# SBC_TMS9918A_ISA.net
KiCad netlist of a schematic drawn in EAGLE
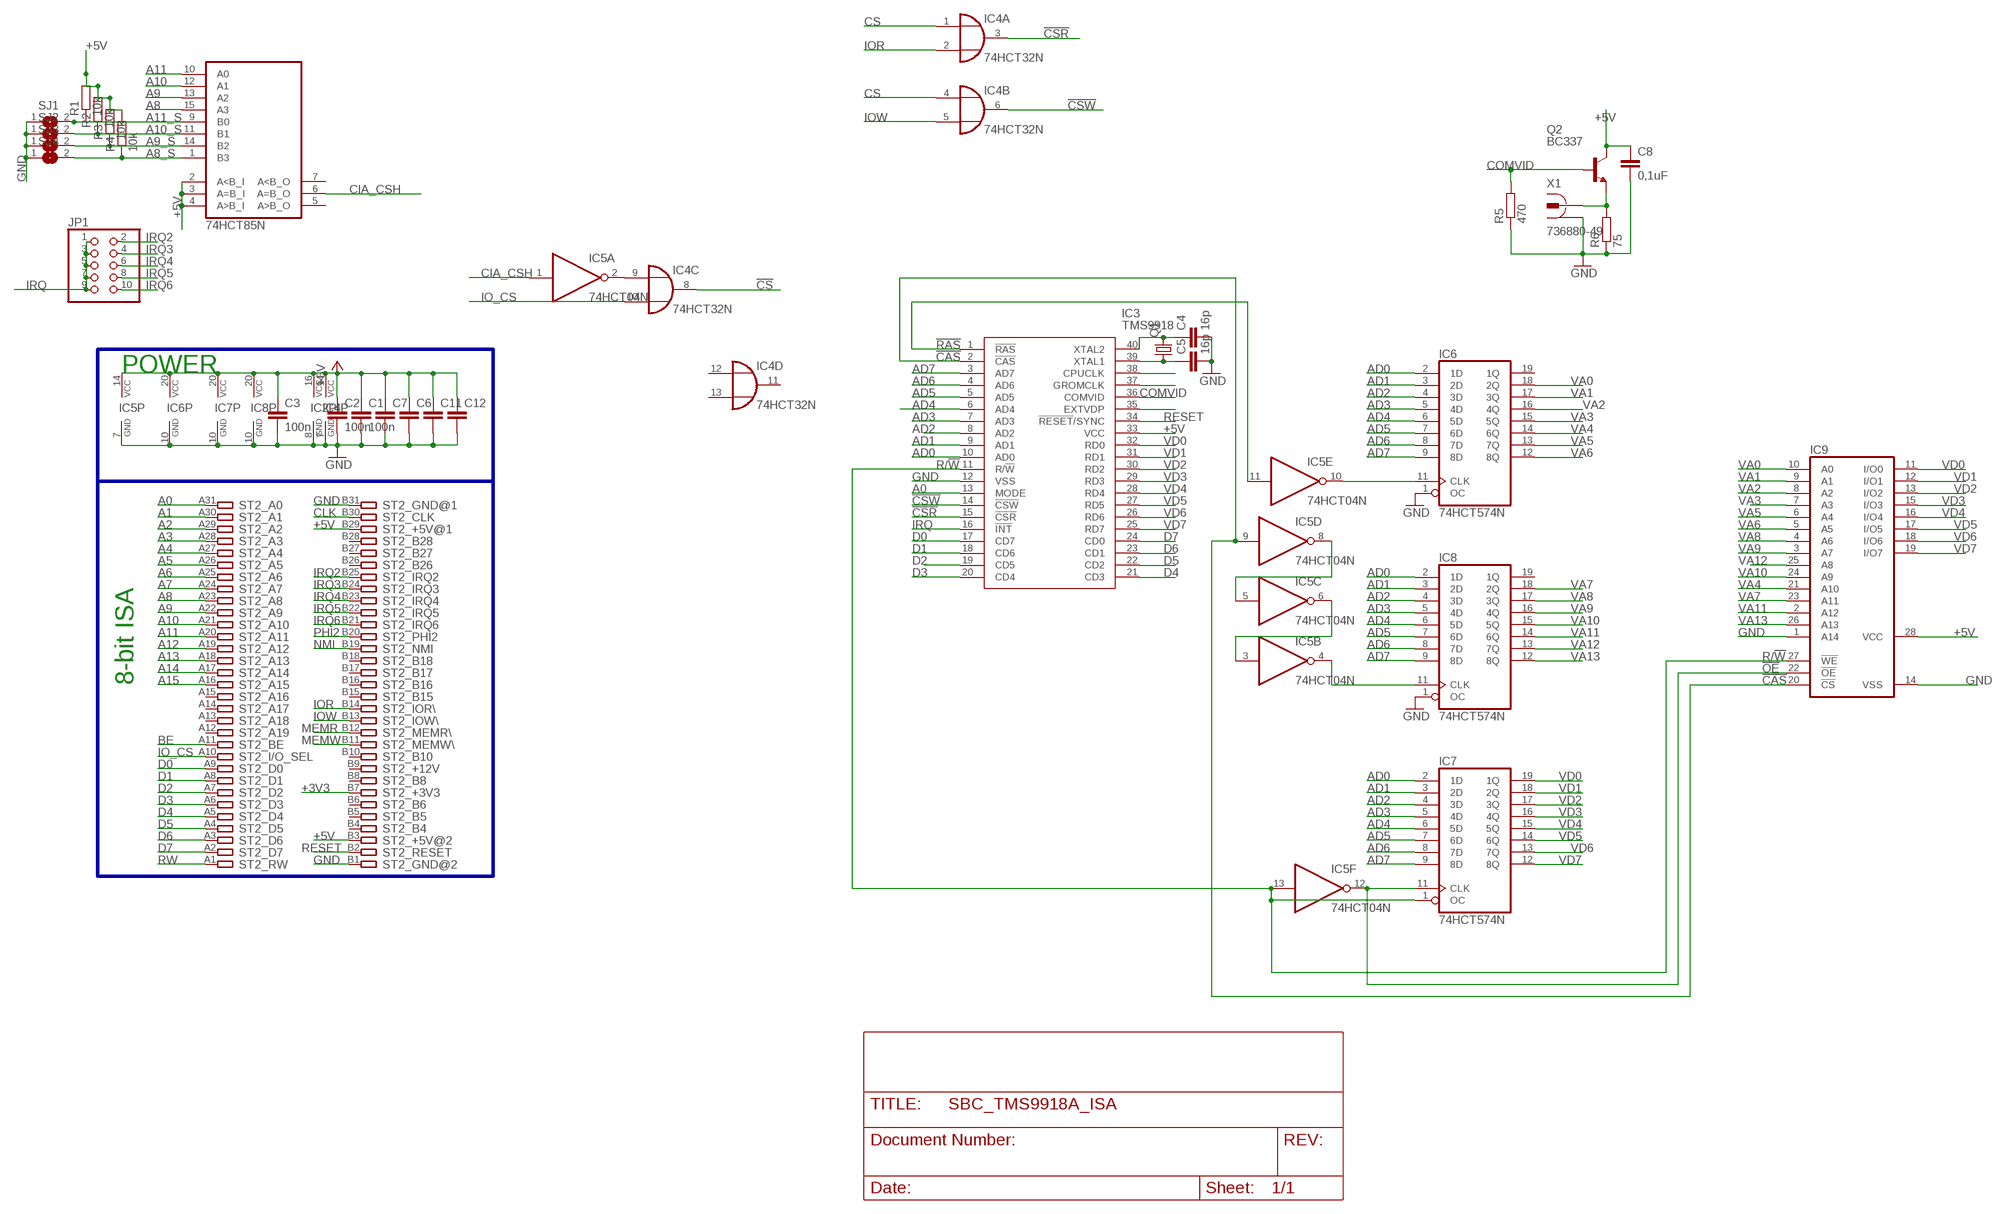
[diagram p0: schematic, sheet 1]

(export (version "E")
  (design (tool "Eeschema 10.0.6"))
  (components
    (comp (ref "C1")
      (value "100n")
      (footprint "eagle-import:C050-025X075")
      (libsource (lib "eagle-import") (part "C-EU050-025X075"))
    )
    (comp (ref "C2")
      (value "100n")
      (footprint "eagle-import:C050-025X075")
      (libsource (lib "eagle-import") (part "C-EU050-025X075"))
    )
    (comp (ref "C3")
      (value "100n")
      (footprint "eagle-import:C050-025X075")
      (libsource (lib "eagle-import") (part "C-EU050-025X075"))
    )
    (comp (ref "C4")
      (value "16p")
      (footprint "eagle-import:C050-024X044")
      (libsource (lib "eagle-import") (part "rcl_334_C-EU050-024X044"))
    )
    (comp (ref "C5")
      (value "16p")
      (footprint "eagle-import:C050-024X044")
      (libsource (lib "eagle-import") (part "rcl_334_C-EU050-024X044"))
    )
    (comp (ref "C6")
      (value "C-EU050-035X075")
      (footprint "eagle-import:C050-035X075")
      (libsource (lib "eagle-import") (part "rcl_334_C-EU050-035X075"))
    )
    (comp (ref "C7")
      (value "C-EU050-035X075")
      (footprint "eagle-import:C050-035X075")
      (libsource (lib "eagle-import") (part "rcl_334_C-EU050-035X075"))
    )
    (comp (ref "C8")
      (value "0,1uF")
      (footprint "eagle-import:C050-024X044")
      (libsource (lib "eagle-import") (part "rcl_334_C-EU050-024X044"))
    )
    (comp (ref "C11")
      (value "C-EU050-035X075")
      (footprint "eagle-import:C050-035X075")
      (libsource (lib "eagle-import") (part "rcl_334_C-EU050-035X075"))
    )
    (comp (ref "C12")
      (value "C-EU050-035X075")
      (footprint "eagle-import:C050-035X075")
      (libsource (lib "eagle-import") (part "rcl_334_C-EU050-035X075"))
    )
    (comp (ref "IC2")
      (value "74HCT85N")
      (footprint "eagle-import:DIL16")
      (libsource (lib "eagle-import") (part "7485NHCT"))
    )
    (comp (ref "IC3")
      (value "TMS9918")
      (footprint "eagle-import:DIP1524W53P254L5310H508Q40N")
      (libsource (lib "eagle-import") (part "TMS9918"))
    )
    (comp (ref "IC4")
      (value "74HCT32N")
      (footprint "eagle-import:DIL14")
      (libsource (lib "eagle-import") (part "7432NHCT"))
    )
    (comp (ref "IC5")
      (value "74HCT04N")
      (footprint "eagle-import:DIL14")
      (libsource (lib "eagle-import") (part "7404NHCT"))
    )
    (comp (ref "IC6")
      (value "74HCT574N")
      (footprint "eagle-import:DIL20")
      (libsource (lib "eagle-import") (part "74574NHCT"))
    )
    (comp (ref "IC7")
      (value "74HCT574N")
      (footprint "eagle-import:DIL20")
      (libsource (lib "eagle-import") (part "74574NHCT"))
    )
    (comp (ref "IC8")
      (value "74HCT574N")
      (footprint "eagle-import:DIL20")
      (libsource (lib "eagle-import") (part "74574NHCT"))
    )
    (comp (ref "IC9")
      (value "62256P")
      (footprint "eagle-import:DIL28-6")
      (libsource (lib "eagle-import") (part "62256P"))
    )
    (comp (ref "JP1")
      (value "PINHD-2X5")
      (footprint "eagle-import:2X05")
      (libsource (lib "eagle-import") (part "PINHD-2X5"))
    )
    (comp (ref "Q1")
      (value "CRYSTALHC49S")
      (footprint "eagle-import:HC49_S")
      (libsource (lib "eagle-import") (part "CRYSTALHC49S"))
    )
    (comp (ref "Q2")
      (value "BC337")
      (footprint "eagle-import:TO92")
      (libsource (lib "eagle-import") (part "BC337"))
    )
    (comp (ref "R1")
      (value "10k")
      (footprint "eagle-import:0207_7")
      (libsource (lib "eagle-import") (part "R-EU_0207/7"))
    )
    (comp (ref "R2")
      (value "10k")
      (footprint "eagle-import:0207_7")
      (libsource (lib "eagle-import") (part "R-EU_0207/7"))
    )
    (comp (ref "R3")
      (value "10k")
      (footprint "eagle-import:0207_7")
      (libsource (lib "eagle-import") (part "R-EU_0207/7"))
    )
    (comp (ref "R4")
      (value "10k")
      (footprint "eagle-import:0207_7")
      (libsource (lib "eagle-import") (part "R-EU_0207/7"))
    )
    (comp (ref "R5")
      (value "470")
      (footprint "eagle-import:0207_7")
      (libsource (lib "eagle-import") (part "R-EU_0207/7"))
    )
    (comp (ref "R6")
      (value "75")
      (footprint "eagle-import:0207_7")
      (libsource (lib "eagle-import") (part "R-EU_0207/7"))
    )
    (comp (ref "SJ1") (value "SJ") (footprint "eagle-import:SJ") (libsource (lib "eagle-import") (part "SJ")))
    (comp (ref "SJ2") (value "SJ") (footprint "eagle-import:SJ") (libsource (lib "eagle-import") (part "SJ")))
    (comp (ref "SJ3") (value "SJ") (footprint "eagle-import:SJ") (libsource (lib "eagle-import") (part "SJ")))
    (comp (ref "SJ4") (value "SJ") (footprint "eagle-import:SJ") (libsource (lib "eagle-import") (part "SJ")))
    (comp (ref "ST2")
      (value "IBM8BIT_ISASHORT")
      (footprint "eagle-import:APP_2X32_SHORT")
      (libsource (lib "eagle-import") (part "IBM8BIT_ISASHORT"))
    )
    (comp (ref "X1")
      (value "736880-49")
      (footprint "eagle-import:736880-49")
      (libsource (lib "eagle-import") (part "736880-49"))
    )
  )
  (nets
    (net (code "1") (name "+5V") (class "Default")
      (node (ref "C1") (pin "1") (pinfunction "1_1") (pintype "passive"))
      (node (ref "C11") (pin "1") (pinfunction "1_1") (pintype "passive"))
      (node (ref "C12") (pin "1") (pinfunction "1_1") (pintype "passive"))
      (node (ref "C2") (pin "1") (pinfunction "1_1") (pintype "passive"))
      (node (ref "C3") (pin "1") (pinfunction "1_1") (pintype "passive"))
      (node (ref "C6") (pin "1") (pinfunction "1_1") (pintype "passive"))
      (node (ref "C7") (pin "1") (pinfunction "1_1") (pintype "passive"))
      (node (ref "C8") (pin "1") (pinfunction "1_1") (pintype "passive"))
      (node (ref "IC2") (pin "16") (pinfunction "VCC_16") (pintype "power_in"))
      (node (ref "IC2") (pin "2") (pinfunction "A<B_I_2") (pintype "input"))
      (node (ref "IC2") (pin "3") (pinfunction "A=B_I_3") (pintype "input"))
      (node (ref "IC2") (pin "4") (pinfunction "A>B_I_4") (pintype "input"))
      (node (ref "IC3") (pin "33") (pinfunction "VCC_33") (pintype "bidirectional"))
      (node (ref "IC4") (pin "14") (pinfunction "VCC_14") (pintype "power_in"))
      (node (ref "IC5") (pin "14") (pinfunction "VCC_14") (pintype "power_in"))
      (node (ref "IC6") (pin "20") (pinfunction "VCC_20") (pintype "power_in"))
      (node (ref "IC7") (pin "20") (pinfunction "VCC_20") (pintype "power_in"))
      (node (ref "IC8") (pin "20") (pinfunction "VCC_20") (pintype "power_in"))
      (node (ref "IC9") (pin "28") (pinfunction "VCC_28") (pintype "power_in"))
      (node (ref "Q2") (pin "3") (pinfunction "C_3") (pintype "passive"))
      (node (ref "R1") (pin "2") (pinfunction "2_2") (pintype "passive"))
      (node (ref "R2") (pin "2") (pinfunction "2_2") (pintype "passive"))
      (node (ref "R3") (pin "2") (pinfunction "2_2") (pintype "passive"))
      (node (ref "R4") (pin "2") (pinfunction "2_2") (pintype "passive"))
      (node (ref "ST2") (pin "B29") (pinfunction "P_B29") (pintype "bidirectional"))
      (node (ref "ST2") (pin "B3") (pinfunction "P_B3") (pintype "bidirectional"))
    )
    (net (code "2") (name "/+3V3") (class "Default")
      (node (ref "ST2") (pin "B7") (pinfunction "P_B7") (pintype "bidirectional"))
    )
    (net (code "3") (name "/A0") (class "Default")
      (node (ref "IC3") (pin "13") (pinfunction "MODE_13") (pintype "bidirectional"))
      (node (ref "ST2") (pin "A31") (pinfunction "P_A31") (pintype "bidirectional"))
    )
    (net (code "4") (name "/A1") (class "Default")
      (node (ref "ST2") (pin "A30") (pinfunction "P_A30") (pintype "bidirectional"))
    )
    (net (code "5") (name "/A2") (class "Default")
      (node (ref "ST2") (pin "A29") (pinfunction "P_A29") (pintype "bidirectional"))
    )
    (net (code "6") (name "/A3") (class "Default")
      (node (ref "ST2") (pin "A28") (pinfunction "P_A28") (pintype "bidirectional"))
    )
    (net (code "7") (name "/A4") (class "Default")
      (node (ref "ST2") (pin "A27") (pinfunction "P_A27") (pintype "bidirectional"))
    )
    (net (code "8") (name "/A5") (class "Default")
      (node (ref "ST2") (pin "A26") (pinfunction "P_A26") (pintype "bidirectional"))
    )
    (net (code "9") (name "/A6") (class "Default")
      (node (ref "ST2") (pin "A25") (pinfunction "P_A25") (pintype "bidirectional"))
    )
    (net (code "10") (name "/A7") (class "Default")
      (node (ref "ST2") (pin "A24") (pinfunction "P_A24") (pintype "bidirectional"))
    )
    (net (code "11") (name "/A8") (class "Default")
      (node (ref "IC2") (pin "15") (pinfunction "A3_15") (pintype "input"))
      (node (ref "ST2") (pin "A23") (pinfunction "P_A23") (pintype "bidirectional"))
    )
    (net (code "12") (name "/A8_S") (class "Default")
      (node (ref "IC2") (pin "1") (pinfunction "B3_1") (pintype "input"))
      (node (ref "R4") (pin "1") (pinfunction "1_1") (pintype "passive"))
      (node (ref "SJ4") (pin "2") (pinfunction "2_2") (pintype "passive"))
    )
    (net (code "13") (name "/A9") (class "Default")
      (node (ref "IC2") (pin "13") (pinfunction "A2_13") (pintype "input"))
      (node (ref "ST2") (pin "A22") (pinfunction "P_A22") (pintype "bidirectional"))
    )
    (net (code "14") (name "/A9_S") (class "Default")
      (node (ref "IC2") (pin "14") (pinfunction "B2_14") (pintype "input"))
      (node (ref "R3") (pin "1") (pinfunction "1_1") (pintype "passive"))
      (node (ref "SJ3") (pin "2") (pinfunction "2_2") (pintype "passive"))
    )
    (net (code "15") (name "/A10") (class "Default")
      (node (ref "IC2") (pin "12") (pinfunction "A1_12") (pintype "input"))
      (node (ref "ST2") (pin "A21") (pinfunction "P_A21") (pintype "bidirectional"))
    )
    (net (code "16") (name "/A10_S") (class "Default")
      (node (ref "IC2") (pin "11") (pinfunction "B1_11") (pintype "input"))
      (node (ref "R2") (pin "1") (pinfunction "1_1") (pintype "passive"))
      (node (ref "SJ2") (pin "2") (pinfunction "2_2") (pintype "passive"))
    )
    (net (code "17") (name "/A11") (class "Default")
      (node (ref "IC2") (pin "10") (pinfunction "A0_10") (pintype "input"))
      (node (ref "ST2") (pin "A20") (pinfunction "P_A20") (pintype "bidirectional"))
    )
    (net (code "18") (name "/A11_S") (class "Default")
      (node (ref "IC2") (pin "9") (pinfunction "B0_9") (pintype "input"))
      (node (ref "R1") (pin "1") (pinfunction "1_1") (pintype "passive"))
      (node (ref "SJ1") (pin "2") (pinfunction "2_2") (pintype "passive"))
    )
    (net (code "19") (name "/A12") (class "Default")
      (node (ref "ST2") (pin "A19") (pinfunction "P_A19") (pintype "bidirectional"))
    )
    (net (code "20") (name "/A13") (class "Default")
      (node (ref "ST2") (pin "A18") (pinfunction "P_A18") (pintype "bidirectional"))
    )
    (net (code "21") (name "/A14") (class "Default")
      (node (ref "ST2") (pin "A17") (pinfunction "P_A17") (pintype "bidirectional"))
    )
    (net (code "22") (name "/A15") (class "Default")
      (node (ref "ST2") (pin "A16") (pinfunction "P_A16") (pintype "bidirectional"))
    )
    (net (code "23") (name "/AD0") (class "Default")
      (node (ref "IC3") (pin "10") (pinfunction "AD0_10") (pintype "bidirectional"))
      (node (ref "IC6") (pin "2") (pinfunction "1D_2") (pintype "input"))
      (node (ref "IC7") (pin "2") (pinfunction "1D_2") (pintype "input"))
      (node (ref "IC8") (pin "2") (pinfunction "1D_2") (pintype "input"))
    )
    (net (code "24") (name "/AD1") (class "Default")
      (node (ref "IC3") (pin "9") (pinfunction "AD1_9") (pintype "bidirectional"))
      (node (ref "IC6") (pin "3") (pinfunction "2D_3") (pintype "input"))
      (node (ref "IC7") (pin "3") (pinfunction "2D_3") (pintype "input"))
      (node (ref "IC8") (pin "3") (pinfunction "2D_3") (pintype "input"))
    )
    (net (code "25") (name "/AD2") (class "Default")
      (node (ref "IC3") (pin "8") (pinfunction "AD2_8") (pintype "bidirectional"))
      (node (ref "IC6") (pin "4") (pinfunction "3D_4") (pintype "input"))
      (node (ref "IC7") (pin "4") (pinfunction "3D_4") (pintype "input"))
      (node (ref "IC8") (pin "4") (pinfunction "3D_4") (pintype "input"))
    )
    (net (code "26") (name "/AD3") (class "Default")
      (node (ref "IC3") (pin "7") (pinfunction "AD3_7") (pintype "bidirectional"))
      (node (ref "IC6") (pin "5") (pinfunction "4D_5") (pintype "input"))
      (node (ref "IC7") (pin "5") (pinfunction "4D_5") (pintype "input"))
      (node (ref "IC8") (pin "5") (pinfunction "4D_5") (pintype "input"))
    )
    (net (code "27") (name "/AD4") (class "Default")
      (node (ref "IC3") (pin "6") (pinfunction "AD4_6") (pintype "bidirectional"))
      (node (ref "IC6") (pin "6") (pinfunction "5D_6") (pintype "input"))
      (node (ref "IC7") (pin "6") (pinfunction "5D_6") (pintype "input"))
      (node (ref "IC8") (pin "6") (pinfunction "5D_6") (pintype "input"))
    )
    (net (code "28") (name "/AD5") (class "Default")
      (node (ref "IC3") (pin "5") (pinfunction "AD5_5") (pintype "bidirectional"))
      (node (ref "IC6") (pin "7") (pinfunction "6D_7") (pintype "input"))
      (node (ref "IC7") (pin "7") (pinfunction "6D_7") (pintype "input"))
      (node (ref "IC8") (pin "7") (pinfunction "6D_7") (pintype "input"))
    )
    (net (code "29") (name "/AD6") (class "Default")
      (node (ref "IC3") (pin "4") (pinfunction "AD6_4") (pintype "bidirectional"))
      (node (ref "IC6") (pin "8") (pinfunction "7D_8") (pintype "input"))
      (node (ref "IC7") (pin "8") (pinfunction "7D_8") (pintype "input"))
      (node (ref "IC8") (pin "8") (pinfunction "7D_8") (pintype "input"))
    )
    (net (code "30") (name "/AD7") (class "Default")
      (node (ref "IC3") (pin "3") (pinfunction "AD7_3") (pintype "bidirectional"))
      (node (ref "IC6") (pin "9") (pinfunction "8D_9") (pintype "input"))
      (node (ref "IC7") (pin "9") (pinfunction "8D_9") (pintype "input"))
      (node (ref "IC8") (pin "9") (pinfunction "8D_9") (pintype "input"))
    )
    (net (code "31") (name "/BE") (class "Default")
      (node (ref "ST2") (pin "A11") (pinfunction "P_A11") (pintype "bidirectional"))
    )
    (net (code "32") (name "/CIA_CSH") (class "Default")
      (node (ref "IC2") (pin "6") (pinfunction "A=B_O_6") (pintype "output"))
      (node (ref "IC5") (pin "1") (pinfunction "I_1") (pintype "input"))
    )
    (net (code "33") (name "/CLK") (class "Default")
      (node (ref "ST2") (pin "B30") (pinfunction "P_B30") (pintype "bidirectional"))
    )
    (net (code "34") (name "/COMVID") (class "Default")
      (node (ref "IC3") (pin "36") (pinfunction "COMVID_36") (pintype "bidirectional"))
      (node (ref "Q2") (pin "2") (pinfunction "B_2") (pintype "passive"))
      (node (ref "R5") (pin "2") (pinfunction "2_2") (pintype "passive"))
    )
    (net (code "35") (name "/CS") (class "Default")
      (node (ref "IC4") (pin "1") (pinfunction "I0_1") (pintype "input"))
      (node (ref "IC4") (pin "4") (pinfunction "I0_4") (pintype "input"))
    )
    (net (code "36") (name "/D0") (class "Default")
      (node (ref "IC3") (pin "17") (pinfunction "CD7_17") (pintype "bidirectional"))
      (node (ref "ST2") (pin "A9") (pinfunction "P_A9") (pintype "bidirectional"))
    )
    (net (code "37") (name "/D1") (class "Default")
      (node (ref "IC3") (pin "18") (pinfunction "CD6_18") (pintype "bidirectional"))
      (node (ref "ST2") (pin "A8") (pinfunction "P_A8") (pintype "bidirectional"))
    )
    (net (code "38") (name "/D2") (class "Default")
      (node (ref "IC3") (pin "19") (pinfunction "CD5_19") (pintype "bidirectional"))
      (node (ref "ST2") (pin "A7") (pinfunction "P_A7") (pintype "bidirectional"))
    )
    (net (code "39") (name "/D3") (class "Default")
      (node (ref "IC3") (pin "20") (pinfunction "CD4_20") (pintype "bidirectional"))
      (node (ref "ST2") (pin "A6") (pinfunction "P_A6") (pintype "bidirectional"))
    )
    (net (code "40") (name "/D4") (class "Default")
      (node (ref "IC3") (pin "21") (pinfunction "CD3_21") (pintype "bidirectional"))
      (node (ref "ST2") (pin "A5") (pinfunction "P_A5") (pintype "bidirectional"))
    )
    (net (code "41") (name "/D5") (class "Default")
      (node (ref "IC3") (pin "22") (pinfunction "CD2_22") (pintype "bidirectional"))
      (node (ref "ST2") (pin "A4") (pinfunction "P_A4") (pintype "bidirectional"))
    )
    (net (code "42") (name "/D6") (class "Default")
      (node (ref "IC3") (pin "23") (pinfunction "CD1_23") (pintype "bidirectional"))
      (node (ref "ST2") (pin "A3") (pinfunction "P_A3") (pintype "bidirectional"))
    )
    (net (code "43") (name "/D7") (class "Default")
      (node (ref "IC3") (pin "24") (pinfunction "CD0_24") (pintype "bidirectional"))
      (node (ref "ST2") (pin "A2") (pinfunction "P_A2") (pintype "bidirectional"))
    )
    (net (code "44") (name "/IOR") (class "Default")
      (node (ref "IC4") (pin "2") (pinfunction "I1_2") (pintype "input"))
      (node (ref "ST2") (pin "B14") (pinfunction "P_B14") (pintype "bidirectional"))
    )
    (net (code "45") (name "/IOW") (class "Default")
      (node (ref "IC4") (pin "5") (pinfunction "I1_5") (pintype "input"))
      (node (ref "ST2") (pin "B13") (pinfunction "P_B13") (pintype "bidirectional"))
    )
    (net (code "46") (name "/IO_CS") (class "Default")
      (node (ref "IC4") (pin "10") (pinfunction "I1_10") (pintype "input"))
      (node (ref "ST2") (pin "A10") (pinfunction "P_A10") (pintype "bidirectional"))
    )
    (net (code "47") (name "/IRQ") (class "Default")
      (node (ref "IC3") (pin "16") (pinfunction "~{INT}_16") (pintype "bidirectional"))
      (node (ref "JP1") (pin "1") (pinfunction "1_1") (pintype "passive"))
      (node (ref "JP1") (pin "3") (pinfunction "3_3") (pintype "passive"))
      (node (ref "JP1") (pin "5") (pinfunction "5_5") (pintype "passive"))
      (node (ref "JP1") (pin "7") (pinfunction "7_7") (pintype "passive"))
      (node (ref "JP1") (pin "9") (pinfunction "9_9") (pintype "passive"))
    )
    (net (code "48") (name "/IRQ2") (class "Default")
      (node (ref "JP1") (pin "2") (pinfunction "2_2") (pintype "passive"))
      (node (ref "ST2") (pin "B25") (pinfunction "P_B25") (pintype "bidirectional"))
    )
    (net (code "49") (name "/IRQ3") (class "Default")
      (node (ref "JP1") (pin "4") (pinfunction "4_4") (pintype "passive"))
      (node (ref "ST2") (pin "B24") (pinfunction "P_B24") (pintype "bidirectional"))
    )
    (net (code "50") (name "/IRQ4") (class "Default")
      (node (ref "JP1") (pin "6") (pinfunction "6_6") (pintype "passive"))
      (node (ref "ST2") (pin "B23") (pinfunction "P_B23") (pintype "bidirectional"))
    )
    (net (code "51") (name "/IRQ5") (class "Default")
      (node (ref "JP1") (pin "8") (pinfunction "8_8") (pintype "passive"))
      (node (ref "ST2") (pin "B22") (pinfunction "P_B22") (pintype "bidirectional"))
    )
    (net (code "52") (name "/IRQ6") (class "Default")
      (node (ref "JP1") (pin "10") (pinfunction "10_10") (pintype "passive"))
      (node (ref "ST2") (pin "B21") (pinfunction "P_B21") (pintype "bidirectional"))
    )
    (net (code "53") (name "/MEMR") (class "Default")
      (node (ref "ST2") (pin "B12") (pinfunction "P_B12") (pintype "bidirectional"))
    )
    (net (code "54") (name "/MEMW") (class "Default")
      (node (ref "ST2") (pin "B11") (pinfunction "P_B11") (pintype "bidirectional"))
    )
    (net (code "55") (name "/NMI") (class "Default")
      (node (ref "ST2") (pin "B19") (pinfunction "P_B19") (pintype "bidirectional"))
    )
    (net (code "56") (name "/PHI2") (class "Default")
      (node (ref "ST2") (pin "B20") (pinfunction "P_B20") (pintype "bidirectional"))
    )
    (net (code "57") (name "/RESET") (class "Default")
      (node (ref "IC3") (pin "34") (pinfunction "~{RESET}/SYNC_34") (pintype "bidirectional"))
      (node (ref "ST2") (pin "B2") (pinfunction "P_B2") (pintype "bidirectional"))
    )
    (net (code "58") (name "/RW") (class "Default")
      (node (ref "ST2") (pin "A1") (pinfunction "P_A1") (pintype "bidirectional"))
    )
    (net (code "59") (name "/R{slash}~{W}") (class "Default")
      (node (ref "IC3") (pin "11") (pinfunction "R/~{W}_11") (pintype "bidirectional"))
      (node (ref "IC5") (pin "13") (pinfunction "I_13") (pintype "input"))
      (node (ref "IC7") (pin "1") (pinfunction "OC_1") (pintype "input"))
      (node (ref "IC9") (pin "27") (pinfunction "~{WE}_27") (pintype "input"))
    )
    (net (code "60") (name "/VA0") (class "Default")
      (node (ref "IC6") (pin "18") (pinfunction "2Q_18") (pintype "tri_state"))
      (node (ref "IC9") (pin "10") (pinfunction "A0_10") (pintype "input"))
    )
    (net (code "61") (name "/VA1") (class "Default")
      (node (ref "IC6") (pin "17") (pinfunction "3Q_17") (pintype "tri_state"))
      (node (ref "IC9") (pin "9") (pinfunction "A1_9") (pintype "input"))
    )
    (net (code "62") (name "/VA2") (class "Default")
      (node (ref "IC6") (pin "16") (pinfunction "4Q_16") (pintype "tri_state"))
      (node (ref "IC9") (pin "8") (pinfunction "A2_8") (pintype "input"))
    )
    (net (code "63") (name "/VA3") (class "Default")
      (node (ref "IC6") (pin "15") (pinfunction "5Q_15") (pintype "tri_state"))
      (node (ref "IC9") (pin "7") (pinfunction "A3_7") (pintype "input"))
    )
    (net (code "64") (name "/VA4") (class "Default")
      (node (ref "IC6") (pin "14") (pinfunction "6Q_14") (pintype "tri_state"))
      (node (ref "IC9") (pin "21") (pinfunction "A10_21") (pintype "input"))
    )
    (net (code "65") (name "/VA5") (class "Default")
      (node (ref "IC6") (pin "13") (pinfunction "7Q_13") (pintype "tri_state"))
      (node (ref "IC9") (pin "6") (pinfunction "A4_6") (pintype "input"))
    )
    (net (code "66") (name "/VA6") (class "Default")
      (node (ref "IC6") (pin "12") (pinfunction "8Q_12") (pintype "tri_state"))
      (node (ref "IC9") (pin "5") (pinfunction "A5_5") (pintype "input"))
    )
    (net (code "67") (name "/VA7") (class "Default")
      (node (ref "IC8") (pin "18") (pinfunction "2Q_18") (pintype "tri_state"))
      (node (ref "IC9") (pin "23") (pinfunction "A11_23") (pintype "input"))
    )
    (net (code "68") (name "/VA8") (class "Default")
      (node (ref "IC8") (pin "17") (pinfunction "3Q_17") (pintype "tri_state"))
      (node (ref "IC9") (pin "4") (pinfunction "A6_4") (pintype "input"))
    )
    (net (code "69") (name "/VA9") (class "Default")
      (node (ref "IC8") (pin "16") (pinfunction "4Q_16") (pintype "tri_state"))
      (node (ref "IC9") (pin "3") (pinfunction "A7_3") (pintype "input"))
    )
    (net (code "70") (name "/VA10") (class "Default")
      (node (ref "IC8") (pin "15") (pinfunction "5Q_15") (pintype "tri_state"))
      (node (ref "IC9") (pin "24") (pinfunction "A9_24") (pintype "input"))
    )
    (net (code "71") (name "/VA11") (class "Default")
      (node (ref "IC8") (pin "14") (pinfunction "6Q_14") (pintype "tri_state"))
      (node (ref "IC9") (pin "2") (pinfunction "A12_2") (pintype "input"))
    )
    (net (code "72") (name "/VA12") (class "Default")
      (node (ref "IC8") (pin "13") (pinfunction "7Q_13") (pintype "tri_state"))
      (node (ref "IC9") (pin "25") (pinfunction "A8_25") (pintype "input"))
    )
    (net (code "73") (name "/VA13") (class "Default")
      (node (ref "IC8") (pin "12") (pinfunction "8Q_12") (pintype "tri_state"))
      (node (ref "IC9") (pin "26") (pinfunction "A13_26") (pintype "input"))
    )
    (net (code "74") (name "/VD0") (class "Default")
      (node (ref "IC3") (pin "32") (pinfunction "RD0_32") (pintype "bidirectional"))
      (node (ref "IC7") (pin "19") (pinfunction "1Q_19") (pintype "tri_state"))
      (node (ref "IC9") (pin "11") (pinfunction "I/O0_11") (pintype "bidirectional"))
    )
    (net (code "75") (name "/VD1") (class "Default")
      (node (ref "IC3") (pin "31") (pinfunction "RD1_31") (pintype "bidirectional"))
      (node (ref "IC7") (pin "18") (pinfunction "2Q_18") (pintype "tri_state"))
      (node (ref "IC9") (pin "12") (pinfunction "I/O1_12") (pintype "bidirectional"))
    )
    (net (code "76") (name "/VD2") (class "Default")
      (node (ref "IC3") (pin "30") (pinfunction "RD2_30") (pintype "bidirectional"))
      (node (ref "IC7") (pin "17") (pinfunction "3Q_17") (pintype "tri_state"))
      (node (ref "IC9") (pin "13") (pinfunction "I/O2_13") (pintype "bidirectional"))
    )
    (net (code "77") (name "/VD3") (class "Default")
      (node (ref "IC3") (pin "29") (pinfunction "RD3_29") (pintype "bidirectional"))
      (node (ref "IC7") (pin "16") (pinfunction "4Q_16") (pintype "tri_state"))
      (node (ref "IC9") (pin "15") (pinfunction "I/O3_15") (pintype "bidirectional"))
    )
    (net (code "78") (name "/VD4") (class "Default")
      (node (ref "IC3") (pin "28") (pinfunction "RD4_28") (pintype "bidirectional"))
      (node (ref "IC7") (pin "15") (pinfunction "5Q_15") (pintype "tri_state"))
      (node (ref "IC9") (pin "16") (pinfunction "I/O4_16") (pintype "bidirectional"))
    )
    (net (code "79") (name "/VD5") (class "Default")
      (node (ref "IC3") (pin "27") (pinfunction "RD5_27") (pintype "bidirectional"))
      (node (ref "IC7") (pin "14") (pinfunction "6Q_14") (pintype "tri_state"))
      (node (ref "IC9") (pin "17") (pinfunction "I/O5_17") (pintype "bidirectional"))
    )
    (net (code "80") (name "/VD6") (class "Default")
      (node (ref "IC3") (pin "26") (pinfunction "RD6_26") (pintype "bidirectional"))
      (node (ref "IC7") (pin "13") (pinfunction "7Q_13") (pintype "tri_state"))
      (node (ref "IC9") (pin "18") (pinfunction "I/O6_18") (pintype "bidirectional"))
    )
    (net (code "81") (name "/VD7") (class "Default")
      (node (ref "IC3") (pin "25") (pinfunction "RD7_25") (pintype "bidirectional"))
      (node (ref "IC7") (pin "12") (pinfunction "8Q_12") (pintype "tri_state"))
      (node (ref "IC9") (pin "19") (pinfunction "I/O7_19") (pintype "bidirectional"))
    )
    (net (code "82") (name "/~{CAS}") (class "Default")
      (node (ref "IC3") (pin "2") (pinfunction "~{CAS}_2") (pintype "bidirectional"))
      (node (ref "IC5") (pin "9") (pinfunction "I_9") (pintype "input"))
      (node (ref "IC9") (pin "20") (pinfunction "~{CS}_20") (pintype "input"))
    )
    (net (code "83") (name "/~{CSR}") (class "Default")
      (node (ref "IC3") (pin "15") (pinfunction "~{CSR}_15") (pintype "bidirectional"))
      (node (ref "IC4") (pin "3") (pinfunction "O_3") (pintype "output"))
    )
    (net (code "84") (name "/~{CSW}") (class "Default")
      (node (ref "IC3") (pin "14") (pinfunction "~{CSW}_14") (pintype "bidirectional"))
      (node (ref "IC4") (pin "6") (pinfunction "O_6") (pintype "output"))
    )
    (net (code "85") (name "/~{CS}") (class "Default")
      (node (ref "IC4") (pin "8") (pinfunction "O_8") (pintype "output"))
    )
    (net (code "86") (name "/~{OE}") (class "Default")
      (node (ref "IC5") (pin "12") (pinfunction "O_12") (pintype "output"))
      (node (ref "IC7") (pin "11") (pinfunction "CLK_11") (pintype "input"))
      (node (ref "IC9") (pin "22") (pinfunction "~{OE}_22") (pintype "input"))
    )
    (net (code "87") (name "/~{RAS}") (class "Default")
      (node (ref "IC3") (pin "1") (pinfunction "~{RAS}_1") (pintype "bidirectional"))
      (node (ref "IC5") (pin "11") (pinfunction "I_11") (pintype "input"))
    )
    (net (code "88") (name "GND") (class "Default")
      (node (ref "C1") (pin "2") (pinfunction "2_2") (pintype "passive"))
      (node (ref "C11") (pin "2") (pinfunction "2_2") (pintype "passive"))
      (node (ref "C12") (pin "2") (pinfunction "2_2") (pintype "passive"))
      (node (ref "C2") (pin "2") (pinfunction "2_2") (pintype "passive"))
      (node (ref "C3") (pin "2") (pinfunction "2_2") (pintype "passive"))
      (node (ref "C4") (pin "2") (pinfunction "2_2") (pintype "passive"))
      (node (ref "C5") (pin "2") (pinfunction "2_2") (pintype "passive"))
      (node (ref "C6") (pin "2") (pinfunction "2_2") (pintype "passive"))
      (node (ref "C7") (pin "2") (pinfunction "2_2") (pintype "passive"))
      (node (ref "C8") (pin "2") (pinfunction "2_2") (pintype "passive"))
      (node (ref "IC2") (pin "8") (pinfunction "GND_8") (pintype "power_in"))
      (node (ref "IC3") (pin "12") (pinfunction "VSS_12") (pintype "bidirectional"))
      (node (ref "IC4") (pin "7") (pinfunction "GND_7") (pintype "power_in"))
      (node (ref "IC5") (pin "7") (pinfunction "GND_7") (pintype "power_in"))
      (node (ref "IC6") (pin "1") (pinfunction "OC_1") (pintype "input"))
      (node (ref "IC6") (pin "10") (pinfunction "GND_10") (pintype "power_in"))
      (node (ref "IC7") (pin "10") (pinfunction "GND_10") (pintype "power_in"))
      (node (ref "IC8") (pin "1") (pinfunction "OC_1") (pintype "input"))
      (node (ref "IC8") (pin "10") (pinfunction "GND_10") (pintype "power_in"))
      (node (ref "IC9") (pin "1") (pinfunction "A14_1") (pintype "input"))
      (node (ref "IC9") (pin "14") (pinfunction "VSS_14") (pintype "power_in"))
      (node (ref "R5") (pin "1") (pinfunction "1_1") (pintype "passive"))
      (node (ref "R6") (pin "1") (pinfunction "1_1") (pintype "passive"))
      (node (ref "SJ1") (pin "1") (pinfunction "1_1") (pintype "passive"))
      (node (ref "SJ2") (pin "1") (pinfunction "1_1") (pintype "passive"))
      (node (ref "SJ3") (pin "1") (pinfunction "1_1") (pintype "passive"))
      (node (ref "SJ4") (pin "1") (pinfunction "1_1") (pintype "passive"))
      (node (ref "ST2") (pin "B1") (pinfunction "P_B1") (pintype "bidirectional"))
      (node (ref "ST2") (pin "B31") (pinfunction "P_B31") (pintype "bidirectional"))
      (node (ref "X1") (pin "1") (pinfunction "1_1") (pintype "passive"))
      (node (ref "X1") (pin "1@1") (pinfunction "1_1@1") (pintype "passive"))
      (node (ref "X1") (pin "1@2") (pinfunction "1_1@2") (pintype "passive"))
    )
    (net (code "89") (name "Net-(IC3-XTAL1)") (class "Default")
      (node (ref "C5") (pin "1") (pinfunction "1_1") (pintype "passive"))
      (node (ref "IC3") (pin "39") (pinfunction "XTAL1_39") (pintype "bidirectional"))
      (node (ref "Q1") (pin "1") (pinfunction "1_1") (pintype "passive"))
    )
    (net (code "90") (name "Net-(IC3-XTAL2)") (class "Default")
      (node (ref "C4") (pin "1") (pinfunction "1_1") (pintype "passive"))
      (node (ref "IC3") (pin "40") (pinfunction "XTAL2_40") (pintype "bidirectional"))
      (node (ref "Q1") (pin "2") (pinfunction "2_2") (pintype "passive"))
    )
    (net (code "91") (name "Net-(IC4C-I0)") (class "Default")
      (node (ref "IC4") (pin "9") (pinfunction "I0_9") (pintype "input"))
      (node (ref "IC5") (pin "2") (pinfunction "O_2") (pintype "output"))
    )
    (net (code "92") (name "Net-(IC5B-I)") (class "Default")
      (node (ref "IC5") (pin "3") (pinfunction "I_3") (pintype "input"))
      (node (ref "IC5") (pin "6") (pinfunction "O_6") (pintype "output"))
    )
    (net (code "93") (name "Net-(IC5B-O)") (class "Default")
      (node (ref "IC5") (pin "4") (pinfunction "O_4") (pintype "output"))
      (node (ref "IC8") (pin "11") (pinfunction "CLK_11") (pintype "input"))
    )
    (net (code "94") (name "Net-(IC5C-I)") (class "Default")
      (node (ref "IC5") (pin "5") (pinfunction "I_5") (pintype "input"))
      (node (ref "IC5") (pin "8") (pinfunction "O_8") (pintype "output"))
    )
    (net (code "95") (name "Net-(IC5E-O)") (class "Default")
      (node (ref "IC5") (pin "10") (pinfunction "O_10") (pintype "output"))
      (node (ref "IC6") (pin "11") (pinfunction "CLK_11") (pintype "input"))
    )
    (net (code "96") (name "Net-(Q2-E)") (class "Default")
      (node (ref "Q2") (pin "1") (pinfunction "E_1") (pintype "passive"))
      (node (ref "R6") (pin "2") (pinfunction "2_2") (pintype "passive"))
      (node (ref "X1") (pin "2") (pinfunction "2_2") (pintype "passive"))
    )
    (net (code "97") (name "unconnected-(IC2A-A<B_O-Pad7)") (class "Default")
      (node (ref "IC2") (pin "7") (pinfunction "A<B_O_7") (pintype "output"))
    )
    (net (code "98") (name "unconnected-(IC2A-A>B_O-Pad5)") (class "Default")
      (node (ref "IC2") (pin "5") (pinfunction "A>B_O_5") (pintype "output"))
    )
    (net (code "99") (name "unconnected-(IC3-CPUCLK-Pad38)") (class "Default")
      (node (ref "IC3") (pin "38") (pinfunction "CPUCLK_38") (pintype "bidirectional"))
    )
    (net (code "100") (name "unconnected-(IC3-EXTVDP-Pad35)") (class "Default")
      (node (ref "IC3") (pin "35") (pinfunction "EXTVDP_35") (pintype "bidirectional"))
    )
    (net (code "101") (name "unconnected-(IC3-GROMCLK-Pad37)") (class "Default")
      (node (ref "IC3") (pin "37") (pinfunction "GROMCLK_37") (pintype "bidirectional"))
    )
    (net (code "102") (name "unconnected-(IC4D-I0-Pad12)") (class "Default")
      (node (ref "IC4") (pin "12") (pinfunction "I0_12") (pintype "input"))
    )
    (net (code "103") (name "unconnected-(IC4D-I1-Pad13)") (class "Default")
      (node (ref "IC4") (pin "13") (pinfunction "I1_13") (pintype "input"))
    )
    (net (code "104") (name "unconnected-(IC4D-O-Pad11)") (class "Default")
      (node (ref "IC4") (pin "11") (pinfunction "O_11") (pintype "output"))
    )
    (net (code "105") (name "unconnected-(IC6A-1Q-Pad19)") (class "Default")
      (node (ref "IC6") (pin "19") (pinfunction "1Q_19") (pintype "tri_state"))
    )
    (net (code "106") (name "unconnected-(IC8A-1Q-Pad19)") (class "Default")
      (node (ref "IC8") (pin "19") (pinfunction "1Q_19") (pintype "tri_state"))
    )
    (net (code "107") (name "unconnected-(ST2A-P-PadB9)") (class "Default")
      (node (ref "ST2") (pin "B9") (pinfunction "P_B9") (pintype "bidirectional"))
    )
    (net (code "108") (name "unconnected-(ST2AA-P-PadB16)") (class "Default")
      (node (ref "ST2") (pin "B16") (pinfunction "P_B16") (pintype "bidirectional"))
    )
    (net (code "109") (name "unconnected-(ST2AB-P-PadB17)") (class "Default")
      (node (ref "ST2") (pin "B17") (pinfunction "P_B17") (pintype "bidirectional"))
    )
    (net (code "110") (name "unconnected-(ST2AC-P-PadB18)") (class "Default")
      (node (ref "ST2") (pin "B18") (pinfunction "P_B18") (pintype "bidirectional"))
    )
    (net (code "111") (name "unconnected-(ST2AD-P-PadB26)") (class "Default")
      (node (ref "ST2") (pin "B26") (pinfunction "P_B26") (pintype "bidirectional"))
    )
    (net (code "112") (name "unconnected-(ST2AE-P-PadB27)") (class "Default")
      (node (ref "ST2") (pin "B27") (pinfunction "P_B27") (pintype "bidirectional"))
    )
    (net (code "113") (name "unconnected-(ST2AF-P-PadB28)") (class "Default")
      (node (ref "ST2") (pin "B28") (pinfunction "P_B28") (pintype "bidirectional"))
    )
    (net (code "114") (name "unconnected-(ST2AG-P-PadB4)") (class "Default")
      (node (ref "ST2") (pin "B4") (pinfunction "P_B4") (pintype "bidirectional"))
    )
    (net (code "115") (name "unconnected-(ST2AH-P-PadB5)") (class "Default")
      (node (ref "ST2") (pin "B5") (pinfunction "P_B5") (pintype "bidirectional"))
    )
    (net (code "116") (name "unconnected-(ST2AI-P-PadB6)") (class "Default")
      (node (ref "ST2") (pin "B6") (pinfunction "P_B6") (pintype "bidirectional"))
    )
    (net (code "117") (name "unconnected-(ST2AJ-P-PadB8)") (class "Default")
      (node (ref "ST2") (pin "B8") (pinfunction "P_B8") (pintype "bidirectional"))
    )
    (net (code "118") (name "unconnected-(ST2M-P-PadA15)") (class "Default")
      (node (ref "ST2") (pin "A15") (pinfunction "P_A15") (pintype "bidirectional"))
    )
    (net (code "119") (name "unconnected-(ST2N-P-PadA14)") (class "Default")
      (node (ref "ST2") (pin "A14") (pinfunction "P_A14") (pintype "bidirectional"))
    )
    (net (code "120") (name "unconnected-(ST2O-P-PadA13)") (class "Default")
      (node (ref "ST2") (pin "A13") (pinfunction "P_A13") (pintype "bidirectional"))
    )
    (net (code "121") (name "unconnected-(ST2P-P-PadA12)") (class "Default")
      (node (ref "ST2") (pin "A12") (pinfunction "P_A12") (pintype "bidirectional"))
    )
    (net (code "122") (name "unconnected-(ST2Y-P-PadB10)") (class "Default")
      (node (ref "ST2") (pin "B10") (pinfunction "P_B10") (pintype "bidirectional"))
    )
    (net (code "123") (name "unconnected-(ST2Z-P-PadB15)") (class "Default")
      (node (ref "ST2") (pin "B15") (pinfunction "P_B15") (pintype "bidirectional"))
    )
  )
)
